# CT310_V1_1.net
KiCad netlist of a schematic drawn in Altium Designer
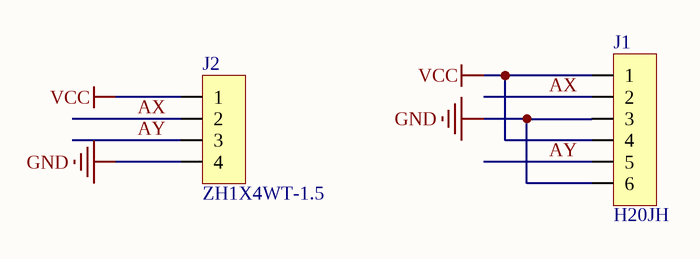
[diagram p0: CT310高端控制盒右摇杆电路V1.1.SchDoc]

(export (version "E")
  (design (tool "Eeschema 10.0.6"))
  (components
    (comp (ref "J1")
      (value "H20JH")
      (footprint "H20JH")
      (libsource (lib "Connector Class") (part "HEADER1X6"))
    )
    (comp (ref "J2")
      (value "ZH1X4WT-1.5")
      (footprint "ZH1X4WT-1.5")
      (libsource (lib "Connector Class") (part "HEADER1X4"))
    )
  )
  (nets
    (net (code "1") (name "/AX") (class "Default")
      (node (ref "J1") (pin "2") (pinfunction "2_2") (pintype "passive"))
      (node (ref "J2") (pin "2") (pinfunction "2_2") (pintype "passive"))
    )
    (net (code "2") (name "/AY") (class "Default")
      (node (ref "J1") (pin "5") (pinfunction "5_5") (pintype "passive"))
      (node (ref "J2") (pin "3") (pinfunction "3_3") (pintype "passive"))
    )
    (net (code "3") (name "GND") (class "Default")
      (node (ref "J1") (pin "3") (pinfunction "3_3") (pintype "passive"))
      (node (ref "J1") (pin "6") (pinfunction "6_6") (pintype "passive"))
      (node (ref "J2") (pin "4") (pinfunction "4_4") (pintype "passive"))
    )
    (net (code "4") (name "VCC") (class "Default")
      (node (ref "J1") (pin "1") (pinfunction "1_1") (pintype "passive"))
      (node (ref "J1") (pin "4") (pinfunction "4_4") (pintype "passive"))
      (node (ref "J2") (pin "1") (pinfunction "1_1") (pintype "passive"))
    )
  )
)
